# ft232.net
KiCad netlist of a schematic drawn in EAGLE
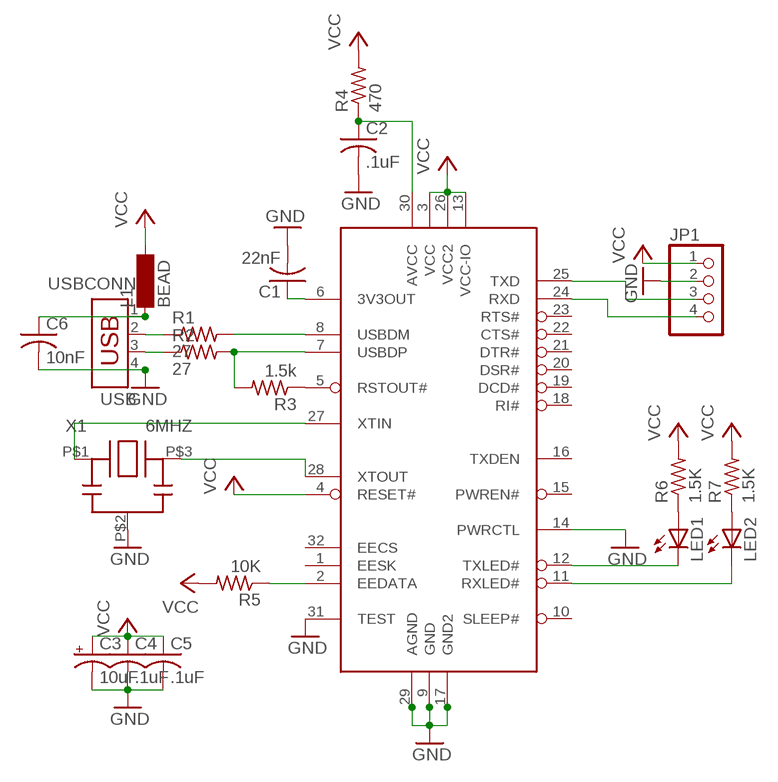
[diagram p0: schematic, sheet 1]

(export (version "E")
  (design (tool "Eeschema 10.0.6"))
  (components
    (comp (ref "C1")
      (value "22nF")
      (footprint "eagle-import:C1206")
      (libsource (lib "eagle-import") (part "C-USC1206"))
    )
    (comp (ref "C2")
      (value ".1uF")
      (footprint "eagle-import:C1206")
      (libsource (lib "eagle-import") (part "C-USC1206"))
    )
    (comp (ref "C3")
      (value "10uF")
      (footprint "eagle-import:B_3528-21R")
      (libsource (lib "eagle-import") (part "CPOL-USB/3528-21R"))
    )
    (comp (ref "C4")
      (value ".1uF")
      (footprint "eagle-import:C1206")
      (libsource (lib "eagle-import") (part "C-USC1206"))
    )
    (comp (ref "C5")
      (value ".1uF")
      (footprint "eagle-import:C1206")
      (libsource (lib "eagle-import") (part "C-USC1206"))
    )
    (comp (ref "C6")
      (value "10nF")
      (footprint "eagle-import:C1206")
      (libsource (lib "eagle-import") (part "C-USC1206"))
    )
    (comp (ref "IC1")
      (value "FT232")
      (footprint "eagle-import:SQFP-S-7X7-32")
      (libsource (lib "eagle-import") (part "FT232"))
    )
    (comp (ref "JP1")
      (value "PINHD-1X4")
      (footprint "eagle-import:1X04")
      (libsource (lib "eagle-import") (part "PINHD-1X4"))
    )
    (comp (ref "L1")
      (value "BEAD")
      (footprint "eagle-import:SM-1206")
      (libsource (lib "eagle-import") (part "SM-1206"))
    )
    (comp (ref "LED1")
      (value "LEDSMT1206")
      (footprint "eagle-import:1206")
      (libsource (lib "eagle-import") (part "LEDSMT1206"))
    )
    (comp (ref "LED2")
      (value "LEDSMT1206")
      (footprint "eagle-import:1206")
      (libsource (lib "eagle-import") (part "LEDSMT1206"))
    )
    (comp (ref "R1")
      (value "27")
      (footprint "eagle-import:R1206")
      (libsource (lib "eagle-import") (part "R-US_R1206"))
    )
    (comp (ref "R2")
      (value "27")
      (footprint "eagle-import:R1206")
      (libsource (lib "eagle-import") (part "R-US_R1206"))
    )
    (comp (ref "R3")
      (value "1.5k")
      (footprint "eagle-import:R1206")
      (libsource (lib "eagle-import") (part "R-US_R1206"))
    )
    (comp (ref "R4")
      (value "470")
      (footprint "eagle-import:R1206")
      (libsource (lib "eagle-import") (part "R-US_R1206"))
    )
    (comp (ref "R5")
      (value "10K")
      (footprint "eagle-import:R1206")
      (libsource (lib "eagle-import") (part "R-US_R1206"))
    )
    (comp (ref "R6")
      (value "1.5K")
      (footprint "eagle-import:R1206")
      (libsource (lib "eagle-import") (part "R-US_R1206"))
    )
    (comp (ref "R7")
      (value "1.5K")
      (footprint "eagle-import:R1206")
      (libsource (lib "eagle-import") (part "R-US_R1206"))
    )
    (comp (ref "USBCONN")
      (value "USB")
      (footprint "eagle-import:USB")
      (libsource (lib "eagle-import") (part "USB"))
    )
    (comp (ref "X1")
      (value "6MHZ")
      (footprint "eagle-import:ZTT_XTAL")
      (libsource (lib "eagle-import") (part "ZTT"))
    )
  )
  (nets
    (net (code "1") (name "GND") (class "Default")
      (node (ref "C1") (pin "2") (pinfunction "2_2") (pintype "passive"))
      (node (ref "C2") (pin "2") (pinfunction "2_2") (pintype "passive"))
      (node (ref "C3") (pin "-") (pinfunction "-_-") (pintype "passive"))
      (node (ref "C4") (pin "2") (pinfunction "2_2") (pintype "passive"))
      (node (ref "C5") (pin "2") (pinfunction "2_2") (pintype "passive"))
      (node (ref "C6") (pin "2") (pinfunction "2_2") (pintype "passive"))
      (node (ref "IC1") (pin "14") (pinfunction "PWRCTL_14") (pintype "bidirectional"))
      (node (ref "IC1") (pin "17") (pinfunction "GND2_17") (pintype "bidirectional"))
      (node (ref "IC1") (pin "29") (pinfunction "AGND_29") (pintype "bidirectional"))
      (node (ref "IC1") (pin "31") (pinfunction "TEST_31") (pintype "bidirectional"))
      (node (ref "IC1") (pin "9") (pinfunction "GND_9") (pintype "bidirectional"))
      (node (ref "JP1") (pin "2") (pinfunction "2_2") (pintype "passive"))
      (node (ref "USBCONN") (pin "4") (pinfunction "4_4") (pintype "passive"))
      (node (ref "X1") (pin "P$2") (pinfunction "GND_P$2") (pintype "bidirectional"))
    )
    (net (code "2") (name "Net-(C6-Pad1)") (class "Default")
      (node (ref "C6") (pin "1") (pinfunction "1_1") (pintype "passive"))
      (node (ref "L1") (pin "1") (pinfunction "1_1") (pintype "passive"))
      (node (ref "USBCONN") (pin "1") (pinfunction "1_1") (pintype "passive"))
    )
    (net (code "3") (name "Net-(IC1-3V3OUT)") (class "Default")
      (node (ref "C1") (pin "1") (pinfunction "1_1") (pintype "passive"))
      (node (ref "IC1") (pin "6") (pinfunction "3V3OUT_6") (pintype "bidirectional"))
    )
    (net (code "4") (name "Net-(IC1-AVCC)") (class "Default")
      (node (ref "C2") (pin "1") (pinfunction "1_1") (pintype "passive"))
      (node (ref "IC1") (pin "30") (pinfunction "AVCC_30") (pintype "bidirectional"))
      (node (ref "R4") (pin "1") (pinfunction "1_1") (pintype "passive"))
    )
    (net (code "5") (name "Net-(IC1-EEDATA)") (class "Default")
      (node (ref "IC1") (pin "2") (pinfunction "EEDATA_2") (pintype "bidirectional"))
      (node (ref "R5") (pin "1") (pinfunction "1_1") (pintype "passive"))
    )
    (net (code "6") (name "Net-(IC1-RSTOUT#)") (class "Default")
      (node (ref "IC1") (pin "5") (pinfunction "RSTOUT#_5") (pintype "bidirectional"))
      (node (ref "R3") (pin "1") (pinfunction "1_1") (pintype "passive"))
    )
    (net (code "7") (name "Net-(IC1-RXD)") (class "Default")
      (node (ref "IC1") (pin "24") (pinfunction "RXD_24") (pintype "bidirectional"))
      (node (ref "JP1") (pin "4") (pinfunction "4_4") (pintype "passive"))
    )
    (net (code "8") (name "Net-(IC1-RXLED#)") (class "Default")
      (node (ref "IC1") (pin "11") (pinfunction "RXLED#_11") (pintype "bidirectional"))
      (node (ref "LED2") (pin "C") (pinfunction "C_C") (pintype "passive"))
    )
    (net (code "9") (name "Net-(IC1-TXD)") (class "Default")
      (node (ref "IC1") (pin "25") (pinfunction "TXD_25") (pintype "bidirectional"))
      (node (ref "JP1") (pin "3") (pinfunction "3_3") (pintype "passive"))
    )
    (net (code "10") (name "Net-(IC1-TXLED#)") (class "Default")
      (node (ref "IC1") (pin "12") (pinfunction "TXLED#_12") (pintype "bidirectional"))
      (node (ref "LED1") (pin "C") (pinfunction "C_C") (pintype "passive"))
    )
    (net (code "11") (name "Net-(IC1-USBDM)") (class "Default")
      (node (ref "IC1") (pin "8") (pinfunction "USBDM_8") (pintype "bidirectional"))
      (node (ref "R1") (pin "2") (pinfunction "2_2") (pintype "passive"))
    )
    (net (code "12") (name "Net-(IC1-USBDP)") (class "Default")
      (node (ref "IC1") (pin "7") (pinfunction "USBDP_7") (pintype "bidirectional"))
      (node (ref "R2") (pin "2") (pinfunction "2_2") (pintype "passive"))
      (node (ref "R3") (pin "2") (pinfunction "2_2") (pintype "passive"))
    )
    (net (code "13") (name "Net-(IC1-XTIN)") (class "Default")
      (node (ref "IC1") (pin "27") (pinfunction "XTIN_27") (pintype "bidirectional"))
      (node (ref "X1") (pin "P$1") (pinfunction "IN_P$1") (pintype "bidirectional"))
    )
    (net (code "14") (name "Net-(IC1-XTOUT)") (class "Default")
      (node (ref "IC1") (pin "28") (pinfunction "XTOUT_28") (pintype "bidirectional"))
      (node (ref "X1") (pin "P$3") (pinfunction "OUT_P$3") (pintype "bidirectional"))
    )
    (net (code "15") (name "Net-(LED1-PadA)") (class "Default")
      (node (ref "LED1") (pin "A") (pinfunction "A_A") (pintype "passive"))
      (node (ref "R6") (pin "1") (pinfunction "1_1") (pintype "passive"))
    )
    (net (code "16") (name "Net-(LED2-PadA)") (class "Default")
      (node (ref "LED2") (pin "A") (pinfunction "A_A") (pintype "passive"))
      (node (ref "R7") (pin "1") (pinfunction "1_1") (pintype "passive"))
    )
    (net (code "17") (name "Net-(R1-Pad1)") (class "Default")
      (node (ref "R1") (pin "1") (pinfunction "1_1") (pintype "passive"))
      (node (ref "USBCONN") (pin "2") (pinfunction "2_2") (pintype "passive"))
    )
    (net (code "18") (name "Net-(R2-Pad1)") (class "Default")
      (node (ref "R2") (pin "1") (pinfunction "1_1") (pintype "passive"))
      (node (ref "USBCONN") (pin "3") (pinfunction "3_3") (pintype "passive"))
    )
    (net (code "19") (name "VCC") (class "Default")
      (node (ref "C3") (pin "+") (pinfunction "+_+") (pintype "passive"))
      (node (ref "C4") (pin "1") (pinfunction "1_1") (pintype "passive"))
      (node (ref "C5") (pin "1") (pinfunction "1_1") (pintype "passive"))
      (node (ref "IC1") (pin "13") (pinfunction "VCC-IO_13") (pintype "bidirectional"))
      (node (ref "IC1") (pin "26") (pinfunction "VCC2_26") (pintype "bidirectional"))
      (node (ref "IC1") (pin "3") (pinfunction "VCC_3") (pintype "bidirectional"))
      (node (ref "IC1") (pin "4") (pinfunction "RESET#_4") (pintype "bidirectional"))
      (node (ref "JP1") (pin "1") (pinfunction "1_1") (pintype "passive"))
      (node (ref "L1") (pin "2") (pinfunction "2_2") (pintype "passive"))
      (node (ref "R4") (pin "2") (pinfunction "2_2") (pintype "passive"))
      (node (ref "R5") (pin "2") (pinfunction "2_2") (pintype "passive"))
      (node (ref "R6") (pin "2") (pinfunction "2_2") (pintype "passive"))
      (node (ref "R7") (pin "2") (pinfunction "2_2") (pintype "passive"))
    )
    (net (code "20") (name "unconnected-(IC1-CTS#-Pad22)") (class "Default")
      (node (ref "IC1") (pin "22") (pinfunction "CTS#_22") (pintype "bidirectional"))
    )
    (net (code "21") (name "unconnected-(IC1-DCD#-Pad19)") (class "Default")
      (node (ref "IC1") (pin "19") (pinfunction "DCD#_19") (pintype "bidirectional"))
    )
    (net (code "22") (name "unconnected-(IC1-DSR#-Pad20)") (class "Default")
      (node (ref "IC1") (pin "20") (pinfunction "DSR#_20") (pintype "bidirectional"))
    )
    (net (code "23") (name "unconnected-(IC1-DTR#-Pad21)") (class "Default")
      (node (ref "IC1") (pin "21") (pinfunction "DTR#_21") (pintype "bidirectional"))
    )
    (net (code "24") (name "unconnected-(IC1-EECS-Pad32)") (class "Default")
      (node (ref "IC1") (pin "32") (pinfunction "EECS_32") (pintype "bidirectional"))
    )
    (net (code "25") (name "unconnected-(IC1-EESK-Pad1)") (class "Default")
      (node (ref "IC1") (pin "1") (pinfunction "EESK_1") (pintype "bidirectional"))
    )
    (net (code "26") (name "unconnected-(IC1-PWREN#-Pad15)") (class "Default")
      (node (ref "IC1") (pin "15") (pinfunction "PWREN#_15") (pintype "bidirectional"))
    )
    (net (code "27") (name "unconnected-(IC1-RI#-Pad18)") (class "Default")
      (node (ref "IC1") (pin "18") (pinfunction "RI#_18") (pintype "bidirectional"))
    )
    (net (code "28") (name "unconnected-(IC1-RTS#-Pad23)") (class "Default")
      (node (ref "IC1") (pin "23") (pinfunction "RTS#_23") (pintype "bidirectional"))
    )
    (net (code "29") (name "unconnected-(IC1-SLEEP#-Pad10)") (class "Default")
      (node (ref "IC1") (pin "10") (pinfunction "SLEEP#_10") (pintype "bidirectional"))
    )
    (net (code "30") (name "unconnected-(IC1-TXDEN-Pad16)") (class "Default")
      (node (ref "IC1") (pin "16") (pinfunction "TXDEN_16") (pintype "bidirectional"))
    )
  )
)
